# 468332_001_Connectors.net
KiCad netlist of a schematic drawn in Altium Designer
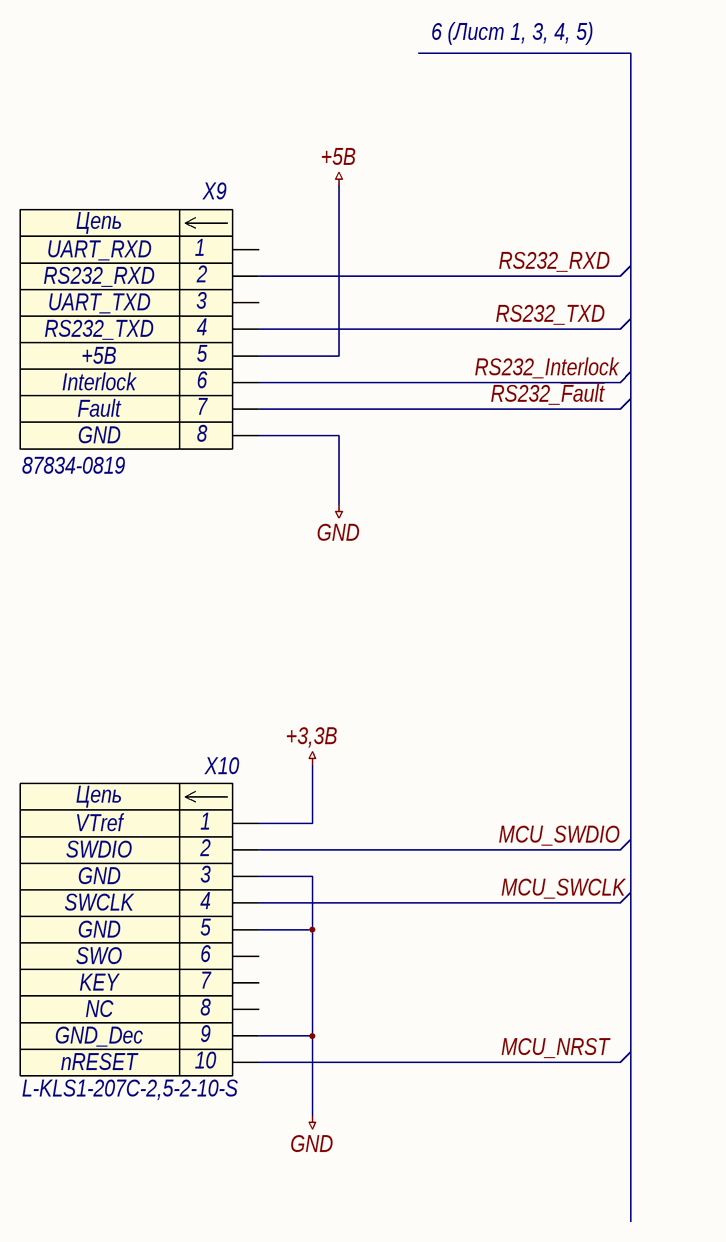
[diagram p0: РЕУН.468332.001_Connectors.SchDoc]

(export (version "E")
  (design (tool "Eeschema 10.0.6"))
  (components
    (comp (ref "X9")
      (value "87834-0819")
      (description "Разъем - 8 конт. вилка")
      (fields (field (name "NAME") "87834-0819"))
      (libsource (lib "Library_Diana") (part "x8-m"))
    )
    (comp (ref "X10")
      (value "L-KLS1-207C-2,5-2-10-S")
      (description "Разъем - 10 конт. вилка")
      (fields (field (name "NAME") "L-KLS1-207C-2,5-2-10-S"))
      (libsource (lib "Library_Diana") (part "x10-m"))
    )
  )
  (nets
    (net (code "1") (name "+3,3В") (class "Default")
      (node (ref "X10") (pin "1") (pinfunction "1_1") (pintype "passive"))
    )
    (net (code "2") (name "+5В") (class "Default")
      (node (ref "X9") (pin "5") (pinfunction "5_5") (pintype "passive"))
    )
    (net (code "3") (name "/MCU_NRST") (class "Default")
      (node (ref "X10") (pin "10") (pinfunction "10_10") (pintype "passive"))
    )
    (net (code "4") (name "/MCU_SWCLK") (class "Default")
      (node (ref "X10") (pin "4") (pinfunction "4_4") (pintype "passive"))
    )
    (net (code "5") (name "/MCU_SWDIO") (class "Default")
      (node (ref "X10") (pin "2") (pinfunction "2_2") (pintype "passive"))
    )
    (net (code "6") (name "/RS232_Interlock") (class "Default")
      (node (ref "X9") (pin "6") (pinfunction "6_6") (pintype "passive"))
    )
    (net (code "7") (name "/RS232_RXD") (class "Default")
      (node (ref "X9") (pin "2") (pinfunction "2_2") (pintype "passive"))
    )
    (net (code "8") (name "/RS232_TXD") (class "Default")
      (node (ref "X9") (pin "4") (pinfunction "4_4") (pintype "passive"))
    )
    (net (code "9") (name "/RS232_~{Fault}") (class "Default")
      (node (ref "X9") (pin "7") (pinfunction "7_7") (pintype "passive"))
    )
    (net (code "10") (name "GND") (class "Default")
      (node (ref "X10") (pin "3") (pinfunction "3_3") (pintype "passive"))
      (node (ref "X10") (pin "5") (pinfunction "5_5") (pintype "passive"))
      (node (ref "X10") (pin "9") (pinfunction "9_9") (pintype "passive"))
      (node (ref "X9") (pin "8") (pinfunction "8_8") (pintype "passive"))
    )
    (net (code "11") (name "unconnected-(X9-Pad1)") (class "Default")
      (node (ref "X9") (pin "1") (pinfunction "1_1") (pintype "passive"))
    )
    (net (code "12") (name "unconnected-(X9-Pad3)") (class "Default")
      (node (ref "X9") (pin "3") (pinfunction "3_3") (pintype "passive"))
    )
    (net (code "13") (name "unconnected-(X10-Pad6)") (class "Default")
      (node (ref "X10") (pin "6") (pinfunction "6_6") (pintype "passive"))
    )
    (net (code "14") (name "unconnected-(X10-Pad7)") (class "Default")
      (node (ref "X10") (pin "7") (pinfunction "7_7") (pintype "passive"))
    )
    (net (code "15") (name "unconnected-(X10-Pad8)") (class "Default")
      (node (ref "X10") (pin "8") (pinfunction "8_8") (pintype "passive"))
    )
  )
)
